# TTAmp_1T3K_amp_tensometer.net
KiCad netlist of a schematic drawn in Altium Designer
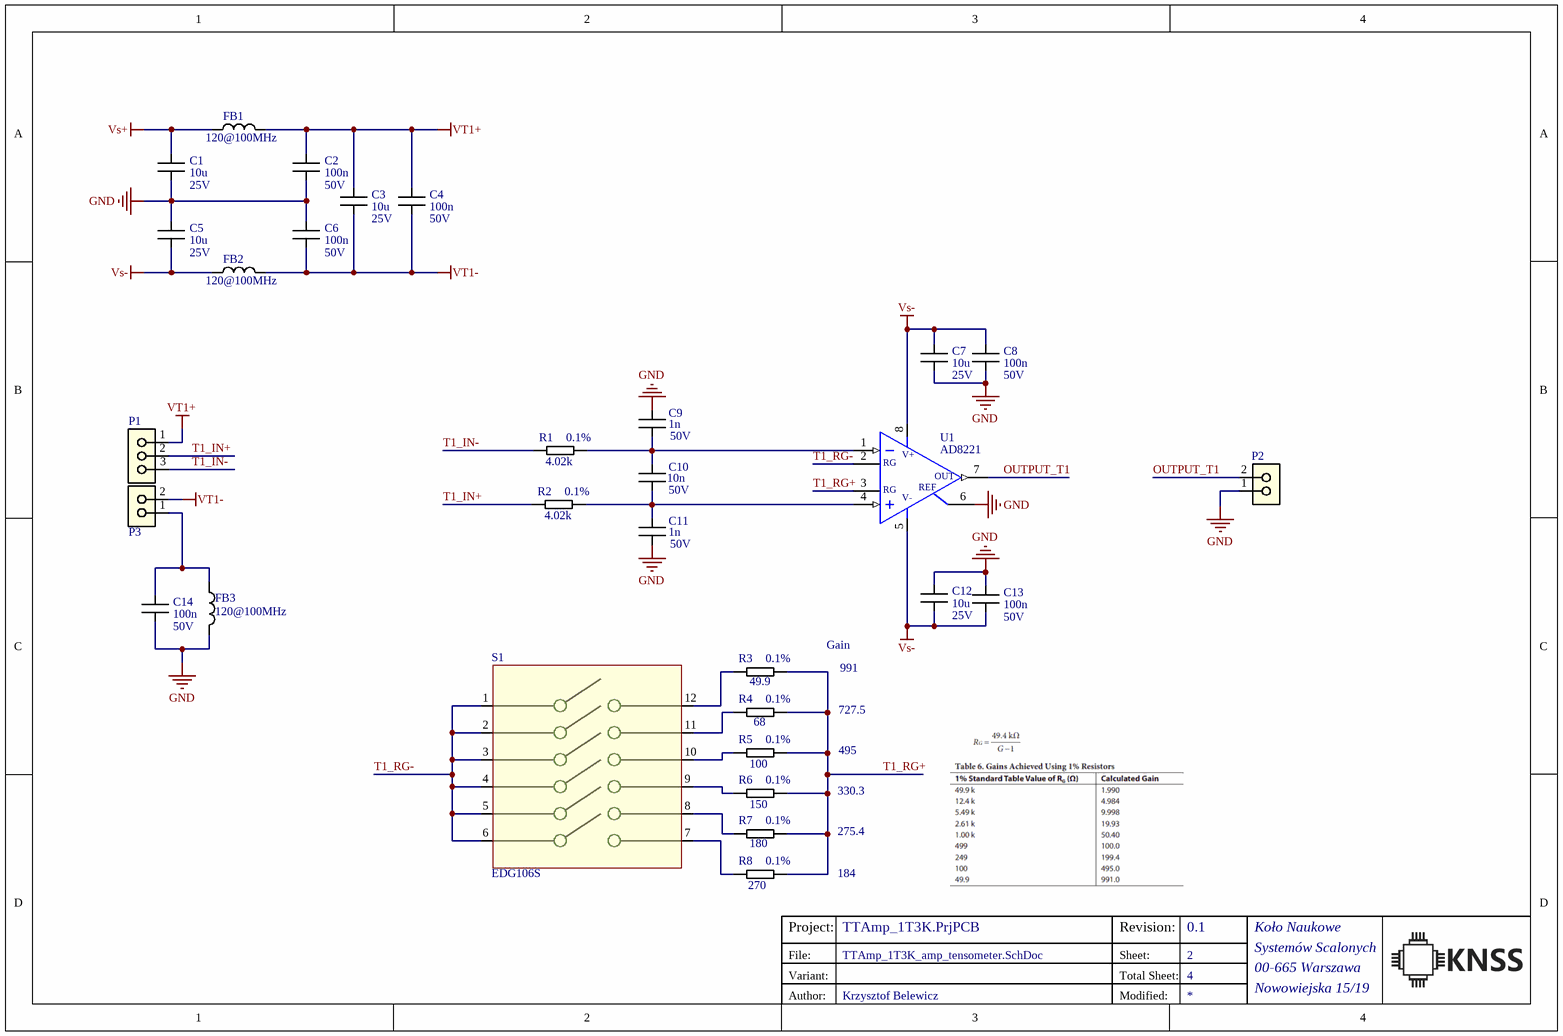
[diagram p0: TTAmp_1T3K_amp_tensometer.SchDoc]

(export (version "E")
  (design (tool "Eeschema 10.0.6"))
  (components
    (comp (ref "C1")
      (value "10u")
      (footprint "CAPC2012N")
      (description "Capacitor")
      (fields (field (name "TOLERANCE") "10%") (field (name "MAXVOLTAGE") "25V"))
      (libsource (lib "RLC") (part "Capacitor"))
    )
    (comp (ref "C2")
      (value "100n")
      (footprint "CAPC1608N")
      (description "Capacitor")
      (fields (field (name "TOLERANCE") "10%") (field (name "MAXVOLTAGE") "50V"))
      (libsource (lib "RLC") (part "Capacitor"))
    )
    (comp (ref "C3")
      (value "10u")
      (footprint "CAPC2012N")
      (description "Capacitor")
      (fields (field (name "TOLERANCE") "10%") (field (name "MAXVOLTAGE") "25V"))
      (libsource (lib "RLC") (part "Capacitor"))
    )
    (comp (ref "C4")
      (value "100n")
      (footprint "CAPC1608N")
      (description "Capacitor")
      (fields (field (name "TOLERANCE") "10%") (field (name "MAXVOLTAGE") "50V"))
      (libsource (lib "RLC") (part "Capacitor"))
    )
    (comp (ref "C5")
      (value "10u")
      (footprint "CAPC2012N")
      (description "Capacitor")
      (fields (field (name "TOLERANCE") "10%") (field (name "MAXVOLTAGE") "25V"))
      (libsource (lib "RLC") (part "Capacitor"))
    )
    (comp (ref "C6")
      (value "100n")
      (footprint "CAPC1608N")
      (description "Capacitor")
      (fields (field (name "TOLERANCE") "10%") (field (name "MAXVOLTAGE") "50V"))
      (libsource (lib "RLC") (part "Capacitor"))
    )
    (comp (ref "C7")
      (value "10u")
      (footprint "CAPC2012N")
      (description "Capacitor")
      (fields (field (name "TOLERANCE") "10%") (field (name "MAXVOLTAGE") "25V"))
      (libsource (lib "RLC") (part "Capacitor"))
    )
    (comp (ref "C8")
      (value "100n")
      (footprint "CAPC1608N")
      (description "Capacitor")
      (fields (field (name "TOLERANCE") "10%") (field (name "MAXVOLTAGE") "50V"))
      (libsource (lib "RLC") (part "Capacitor"))
    )
    (comp (ref "C9")
      (value "1n")
      (footprint "CAPC1608N")
      (description "Capacitor")
      (fields (field (name "TOLERANCE") "10%") (field (name "MAXVOLTAGE") "50V"))
      (libsource (lib "RLC") (part "Capacitor"))
    )
    (comp (ref "C10")
      (value "10n")
      (footprint "CAPC1608N")
      (description "Capacitor")
      (fields (field (name "TOLERANCE") "20%") (field (name "MAXVOLTAGE") "50V"))
      (libsource (lib "RLC") (part "Capacitor"))
    )
    (comp (ref "C11")
      (value "1n")
      (footprint "CAPC1608N")
      (description "Capacitor")
      (fields (field (name "TOLERANCE") "10%") (field (name "MAXVOLTAGE") "50V"))
      (libsource (lib "RLC") (part "Capacitor"))
    )
    (comp (ref "C12")
      (value "10u")
      (footprint "CAPC2012N")
      (description "Capacitor")
      (fields (field (name "TOLERANCE") "10%") (field (name "MAXVOLTAGE") "25V"))
      (libsource (lib "RLC") (part "Capacitor"))
    )
    (comp (ref "C13")
      (value "100n")
      (footprint "CAPC1608N")
      (description "Capacitor")
      (fields (field (name "TOLERANCE") "10%") (field (name "MAXVOLTAGE") "50V"))
      (libsource (lib "RLC") (part "Capacitor"))
    )
    (comp (ref "C14")
      (value "100n")
      (footprint "CAPC1608N")
      (description "Capacitor")
      (fields (field (name "TOLERANCE") "10%") (field (name "MAXVOLTAGE") "50V"))
      (libsource (lib "RLC") (part "Capacitor"))
    )
    (comp (ref "FB1")
      (value "120@100MHz")
      (footprint "INDC1608N")
      (description "Ferrite Bead")
      (libsource (lib "") (part "Inductor_1"))
    )
    (comp (ref "FB2")
      (value "120@100MHz")
      (footprint "INDC1608N")
      (description "Ferrite Bead")
      (libsource (lib "") (part "Inductor_1"))
    )
    (comp (ref "FB3")
      (value "120@100MHz")
      (footprint "INDC1608N")
      (description "Ferrite Bead")
      (libsource (lib "RLC") (part "Inductor"))
    )
    (comp (ref "P1")
      (value "AK100/3DS-5,0-V/GRAU")
      (footprint "AK100/3DS-5,0-V/GRAU")
      (description "Listwa zaciskowa do druku; kątowe 90°; 5mm; tory:3; na PCB; 24A")
      (fields (field (name "MANUFACTURER") "PTR MESSTECHNIK"))
      (libsource (lib "Screw Terminals") (part "AK100/3DS-5,0-V/GRAU"))
    )
    (comp (ref "P2")
      (value "AK100/2DS-5,0-V/GRAU")
      (footprint "AK100/2DS-5,0-V/GRAU")
      (description "Listwa zaciskowa do druku; kątowe 90°; 5mm; tory:2; na PCB; 24A")
      (fields (field (name "MANUFACTURER") "PTR MESSTECHNIK"))
      (libsource (lib "Screw Terminals") (part "AK100/2DS-5,0-V/GRAU"))
    )
    (comp (ref "P3")
      (value "AK100/2DS-5,0-V/GRAU")
      (footprint "AK100/2DS-5,0-V/GRAU")
      (description "Listwa zaciskowa do druku; kątowe 90°; 5mm; tory:2; na PCB; 24A")
      (fields (field (name "MANUFACTURER") "PTR MESSTECHNIK"))
      (libsource (lib "") (part "AK100/2DS-5,0-V/GRAU_1"))
    )
    (comp (ref "R1")
      (value "4.02k")
      (footprint "RESC1608N")
      (description "Resistor")
      (fields (field (name "TOLERANCE") "0.1%") (field (name "POWER") "0.1W"))
      (libsource (lib "RLC") (part "Resistor"))
    )
    (comp (ref "R2")
      (value "4.02k")
      (footprint "RESC1608N")
      (description "Resistor")
      (fields (field (name "TOLERANCE") "0.1%") (field (name "POWER") "0.1W"))
      (libsource (lib "RLC") (part "Resistor"))
    )
    (comp (ref "R3")
      (value "49.9")
      (footprint "RESC1608N")
      (description "Resistor")
      (fields (field (name "TOLERANCE") "0.1%") (field (name "POWER") "0.1W"))
      (libsource (lib "RLC") (part "Resistor"))
    )
    (comp (ref "R4")
      (value "68")
      (footprint "RESC1608N")
      (description "Resistor")
      (fields
        (field (name "TOLERANCE") "0.1%")
        (field (name "POWER") "0.1W")
        (field (name "MANUFACTURER") "VIKING")
      )
      (libsource (lib "RLC") (part "Resistor"))
    )
    (comp (ref "R5")
      (value "100")
      (footprint "RESC1608N")
      (description "Resistor")
      (fields (field (name "TOLERANCE") "0.1%") (field (name "POWER") "0.1W"))
      (libsource (lib "RLC") (part "Resistor"))
    )
    (comp (ref "R6")
      (value "150")
      (footprint "RESC1608N")
      (description "Resistor")
      (fields (field (name "TOLERANCE") "0.1%") (field (name "POWER") "0.1W"))
      (libsource (lib "RLC") (part "Resistor"))
    )
    (comp (ref "R7")
      (value "180")
      (footprint "RESC1608N")
      (description "Resistor")
      (fields (field (name "TOLERANCE") "0.1%") (field (name "POWER") "0.1W"))
      (libsource (lib "RLC") (part "Resistor"))
    )
    (comp (ref "R8")
      (value "270")
      (footprint "RESC1608N")
      (description "Resistor")
      (fields (field (name "TOLERANCE") "0.1%") (field (name "POWER") "0.1W"))
      (libsource (lib "RLC") (part "Resistor"))
    )
    (comp (ref "S1")
      (value "EDG106S")
      (description "Przełącznik: DIP-SWITCH; Ilość sekcji:6; ON-OFF; 0,1A/24VDC; 500V")
      (libsource (lib "ECE") (part "EDG106S"))
    )
    (comp (ref "U1")
      (value "AD8221")
      (footprint "R-8_N")
      (description "Precision Instrumentation Amplifier")
      (libsource (lib "AD Instrumentation Amplifier") (part "AD8221"))
    )
  )
  (nets
    (net (code "1") (name "/OUTPUT_T1") (class "Default")
      (node (ref "P2") (pin "2") (pinfunction "2_2") (pintype "passive"))
      (node (ref "U1") (pin "7") (pinfunction "OUT_7") (pintype "output"))
    )
    (net (code "2") (name "/T1_IN+") (class "Default")
      (node (ref "P1") (pin "2") (pinfunction "2_2") (pintype "passive"))
      (node (ref "R2") (pin "2") (pinfunction "2_2") (pintype "passive"))
    )
    (net (code "3") (name "/T1_IN-") (class "Default")
      (node (ref "P1") (pin "3") (pinfunction "3_3") (pintype "passive"))
      (node (ref "R1") (pin "2") (pinfunction "2_2") (pintype "passive"))
    )
    (net (code "4") (name "/T1_RG+") (class "Default")
      (node (ref "R3") (pin "1") (pinfunction "1_1") (pintype "passive"))
      (node (ref "R4") (pin "1") (pinfunction "1_1") (pintype "passive"))
      (node (ref "R5") (pin "1") (pinfunction "1_1") (pintype "passive"))
      (node (ref "R6") (pin "1") (pinfunction "1_1") (pintype "passive"))
      (node (ref "R7") (pin "1") (pinfunction "1_1") (pintype "passive"))
      (node (ref "R8") (pin "1") (pinfunction "1_1") (pintype "passive"))
      (node (ref "U1") (pin "3") (pinfunction "RG_3") (pintype "passive"))
    )
    (net (code "5") (name "/T1_RG-") (class "Default")
      (node (ref "S1") (pin "1") (pinfunction "1_1") (pintype "passive"))
      (node (ref "S1") (pin "2") (pinfunction "2_2") (pintype "passive"))
      (node (ref "S1") (pin "3") (pinfunction "3_3") (pintype "passive"))
      (node (ref "S1") (pin "4") (pinfunction "4_4") (pintype "passive"))
      (node (ref "S1") (pin "5") (pinfunction "5_5") (pintype "passive"))
      (node (ref "S1") (pin "6") (pinfunction "6_6") (pintype "passive"))
      (node (ref "U1") (pin "2") (pinfunction "RG_2") (pintype "passive"))
    )
    (net (code "6") (name "GND") (class "Default")
      (node (ref "C1") (pin "1") (pinfunction "1_1") (pintype "passive"))
      (node (ref "C11") (pin "1") (pinfunction "1_1") (pintype "passive"))
      (node (ref "C12") (pin "2") (pinfunction "2_2") (pintype "passive"))
      (node (ref "C13") (pin "2") (pinfunction "2_2") (pintype "passive"))
      (node (ref "C14") (pin "1") (pinfunction "1_1") (pintype "passive"))
      (node (ref "C2") (pin "1") (pinfunction "1_1") (pintype "passive"))
      (node (ref "C5") (pin "2") (pinfunction "2_2") (pintype "passive"))
      (node (ref "C6") (pin "2") (pinfunction "2_2") (pintype "passive"))
      (node (ref "C7") (pin "1") (pinfunction "1_1") (pintype "passive"))
      (node (ref "C8") (pin "1") (pinfunction "1_1") (pintype "passive"))
      (node (ref "C9") (pin "2") (pinfunction "2_2") (pintype "passive"))
      (node (ref "FB3") (pin "2") (pinfunction "2_2") (pintype "passive"))
      (node (ref "P2") (pin "1") (pinfunction "1_1") (pintype "passive"))
      (node (ref "U1") (pin "6") (pinfunction "REF_6") (pintype "passive"))
    )
    (net (code "7") (name "Net-(C14-Pad2)") (class "Default")
      (node (ref "C14") (pin "2") (pinfunction "2_2") (pintype "passive"))
      (node (ref "FB3") (pin "1") (pinfunction "1_1") (pintype "passive"))
      (node (ref "P3") (pin "1") (pinfunction "1_1") (pintype "passive"))
    )
    (net (code "8") (name "Net-(R3-Pad2)") (class "Default")
      (node (ref "R3") (pin "2") (pinfunction "2_2") (pintype "passive"))
      (node (ref "S1") (pin "12") (pinfunction "12_12") (pintype "passive"))
    )
    (net (code "9") (name "Net-(R4-Pad2)") (class "Default")
      (node (ref "R4") (pin "2") (pinfunction "2_2") (pintype "passive"))
      (node (ref "S1") (pin "11") (pinfunction "11_11") (pintype "passive"))
    )
    (net (code "10") (name "Net-(R5-Pad2)") (class "Default")
      (node (ref "R5") (pin "2") (pinfunction "2_2") (pintype "passive"))
      (node (ref "S1") (pin "10") (pinfunction "10_10") (pintype "passive"))
    )
    (net (code "11") (name "Net-(R6-Pad2)") (class "Default")
      (node (ref "R6") (pin "2") (pinfunction "2_2") (pintype "passive"))
      (node (ref "S1") (pin "9") (pinfunction "11_9") (pintype "passive"))
    )
    (net (code "12") (name "Net-(R7-Pad2)") (class "Default")
      (node (ref "R7") (pin "2") (pinfunction "2_2") (pintype "passive"))
      (node (ref "S1") (pin "8") (pinfunction "12_8") (pintype "passive"))
    )
    (net (code "13") (name "Net-(S1-13)") (class "Default")
      (node (ref "R8") (pin "2") (pinfunction "2_2") (pintype "passive"))
      (node (ref "S1") (pin "7") (pinfunction "13_7") (pintype "passive"))
    )
    (net (code "14") (name "Net-(U1-+IN)") (class "Default")
      (node (ref "C10") (pin "1") (pinfunction "1_1") (pintype "passive"))
      (node (ref "C11") (pin "2") (pinfunction "2_2") (pintype "passive"))
      (node (ref "R2") (pin "1") (pinfunction "1_1") (pintype "passive"))
      (node (ref "U1") (pin "4") (pinfunction "+IN_4") (pintype "input"))
    )
    (net (code "15") (name "Net-(U1--IN)") (class "Default")
      (node (ref "C10") (pin "2") (pinfunction "2_2") (pintype "passive"))
      (node (ref "C9") (pin "1") (pinfunction "1_1") (pintype "passive"))
      (node (ref "R1") (pin "1") (pinfunction "1_1") (pintype "passive"))
      (node (ref "U1") (pin "1") (pinfunction "-IN_1") (pintype "input"))
    )
    (net (code "16") (name "VT1+") (class "Default")
      (node (ref "C2") (pin "2") (pinfunction "2_2") (pintype "passive"))
      (node (ref "C3") (pin "2") (pinfunction "2_2") (pintype "passive"))
      (node (ref "C4") (pin "2") (pinfunction "2_2") (pintype "passive"))
      (node (ref "FB1") (pin "1") (pinfunction "1_1") (pintype "passive"))
      (node (ref "P1") (pin "1") (pinfunction "1_1") (pintype "passive"))
    )
    (net (code "17") (name "VT1-") (class "Default")
      (node (ref "C3") (pin "1") (pinfunction "1_1") (pintype "passive"))
      (node (ref "C4") (pin "1") (pinfunction "1_1") (pintype "passive"))
      (node (ref "C6") (pin "1") (pinfunction "1_1") (pintype "passive"))
      (node (ref "FB2") (pin "1") (pinfunction "1_1") (pintype "passive"))
      (node (ref "P3") (pin "2") (pinfunction "2_2") (pintype "passive"))
    )
    (net (code "18") (name "Vs+") (class "Default")
      (node (ref "C1") (pin "2") (pinfunction "2_2") (pintype "passive"))
      (node (ref "FB1") (pin "2") (pinfunction "2_2") (pintype "passive"))
    )
    (net (code "19") (name "Vs-") (class "Default")
      (node (ref "C12") (pin "1") (pinfunction "1_1") (pintype "passive"))
      (node (ref "C13") (pin "1") (pinfunction "1_1") (pintype "passive"))
      (node (ref "C5") (pin "1") (pinfunction "1_1") (pintype "passive"))
      (node (ref "C7") (pin "2") (pinfunction "2_2") (pintype "passive"))
      (node (ref "C8") (pin "2") (pinfunction "2_2") (pintype "passive"))
      (node (ref "FB2") (pin "2") (pinfunction "2_2") (pintype "passive"))
      (node (ref "U1") (pin "5") (pinfunction "V-_5") (pintype "power_in"))
      (node (ref "U1") (pin "8") (pinfunction "V+_8") (pintype "power_in"))
    )
  )
)
